# untitled.net
KiCad netlist of a schematic drawn in EAGLE
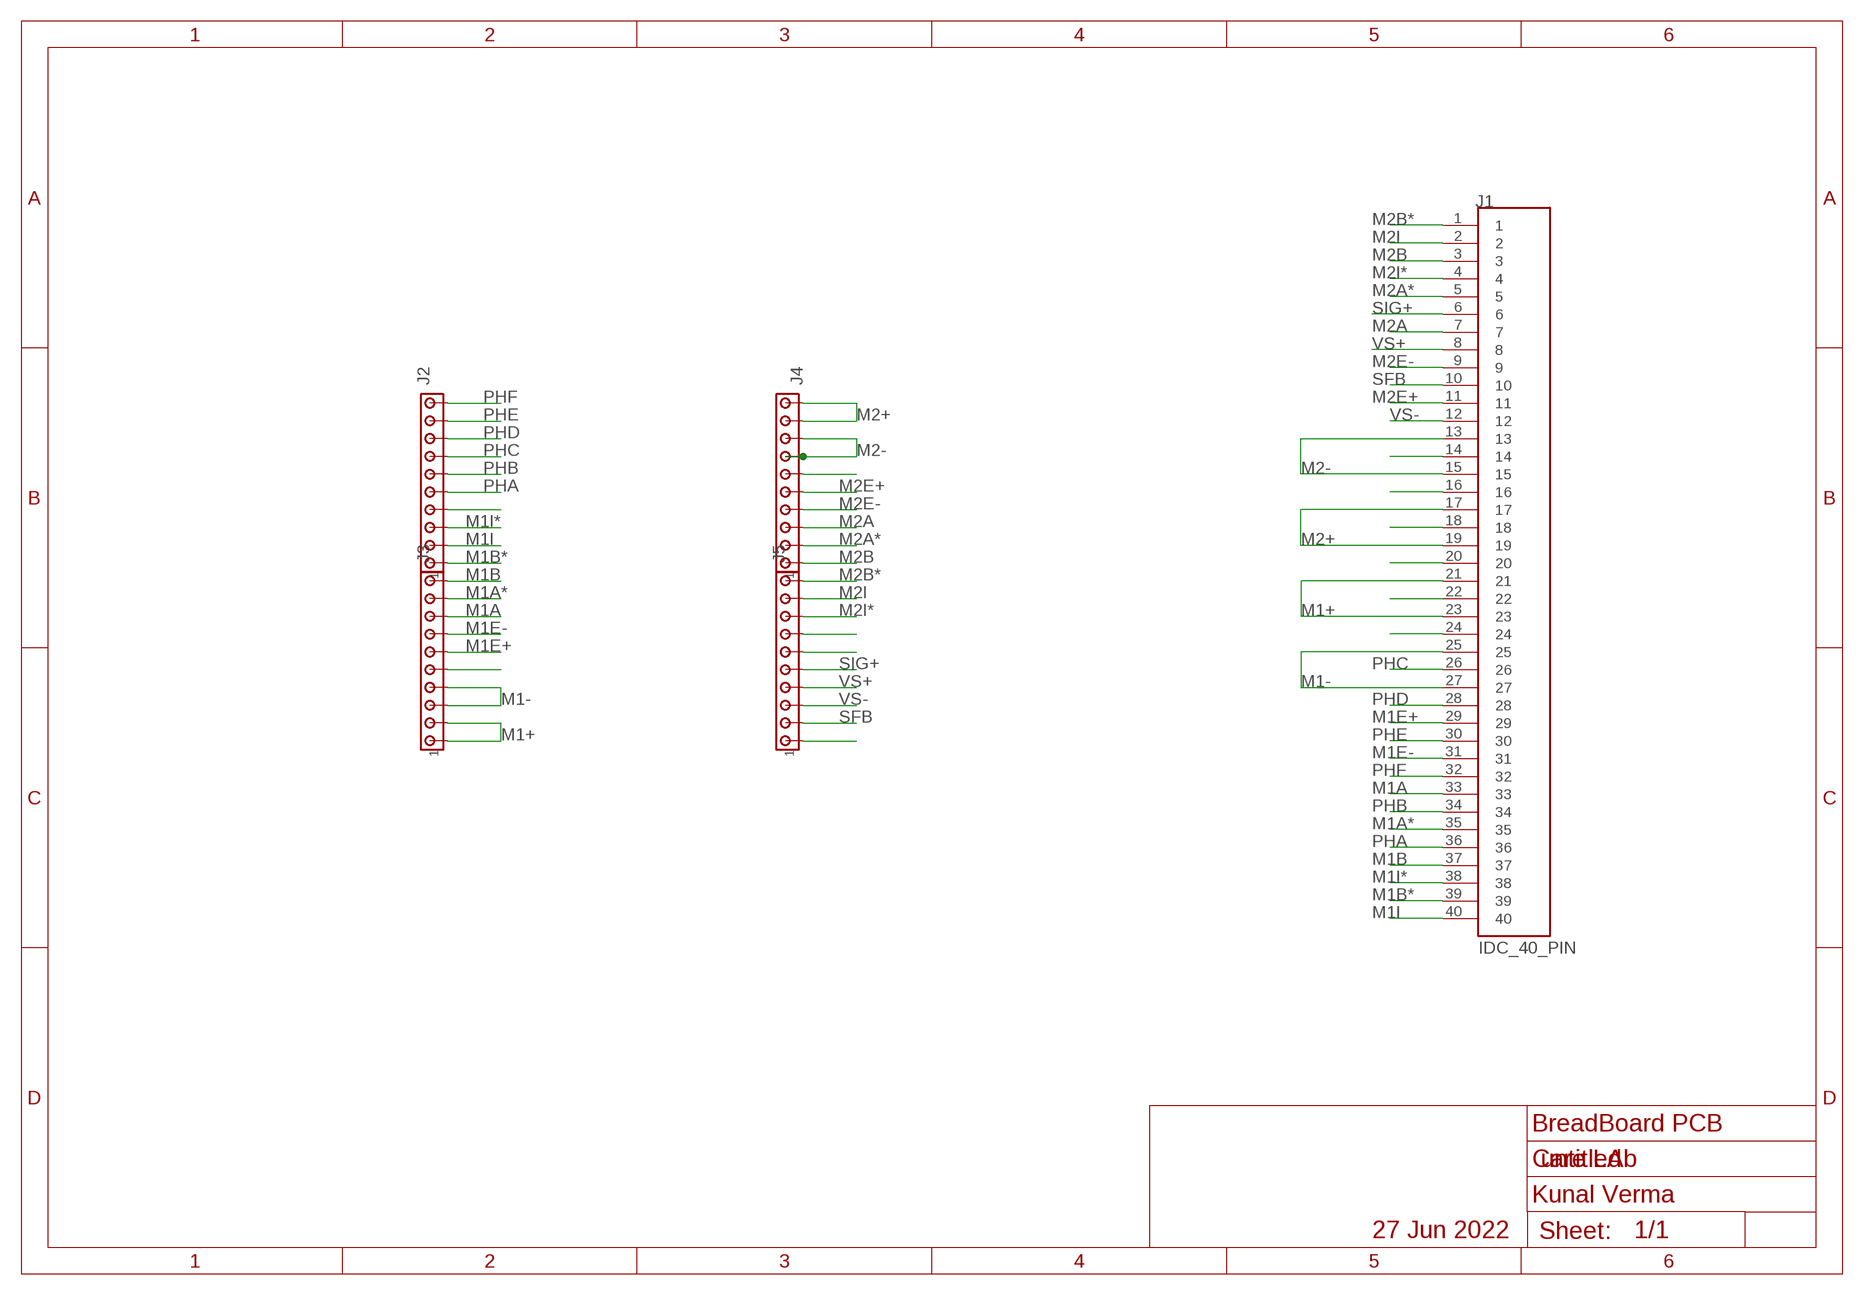
[diagram p0: schematic, sheet 1]

(export (version "E")
  (design (tool "Eeschema 10.0.6"))
  (components
    (comp (ref "J1")
      (value "IDC_40_PIN")
      (footprint "eagle-import:TE_3-1761605-3")
      (fields (field (name "COMMENT") "3-1761605-3") (field (name "MF") "TE Connectivity"))
      (libsource (lib "eagle-import") (part "IDC_40_PIN"))
    )
    (comp (ref "J2")
      (value "MTA10-100")
      (footprint "eagle-import:10X10MTA")
      (libsource (lib "eagle-import") (part "MTA10-100"))
    )
    (comp (ref "J3")
      (value "MTA10-100")
      (footprint "eagle-import:10X10MTA")
      (libsource (lib "eagle-import") (part "MTA10-100"))
    )
    (comp (ref "J4")
      (value "MTA10-100")
      (footprint "eagle-import:10X10MTA")
      (libsource (lib "eagle-import") (part "MTA10-100"))
    )
    (comp (ref "J5")
      (value "MTA10-100")
      (footprint "eagle-import:10X10MTA")
      (libsource (lib "eagle-import") (part "MTA10-100"))
    )
  )
  (nets
    (net (code "1") (name "/M1+") (class "Default")
      (node (ref "J1") (pin "21") (pinfunction "21_21") (pintype "passive"))
      (node (ref "J1") (pin "23") (pinfunction "23_23") (pintype "passive"))
      (node (ref "J3") (pin "1") (pinfunction "1_1") (pintype "passive"))
      (node (ref "J3") (pin "2") (pinfunction "2_2") (pintype "passive"))
    )
    (net (code "2") (name "/M1-") (class "Default")
      (node (ref "J1") (pin "25") (pinfunction "25_25") (pintype "passive"))
      (node (ref "J1") (pin "27") (pinfunction "27_27") (pintype "passive"))
      (node (ref "J3") (pin "3") (pinfunction "3_3") (pintype "passive"))
      (node (ref "J3") (pin "4") (pinfunction "4_4") (pintype "passive"))
    )
    (net (code "3") (name "/M1A") (class "Default")
      (node (ref "J1") (pin "33") (pinfunction "33_33") (pintype "passive"))
      (node (ref "J3") (pin "8") (pinfunction "8_8") (pintype "passive"))
    )
    (net (code "4") (name "/M1A*") (class "Default")
      (node (ref "J1") (pin "35") (pinfunction "35_35") (pintype "passive"))
      (node (ref "J3") (pin "9") (pinfunction "9_9") (pintype "passive"))
    )
    (net (code "5") (name "/M1B") (class "Default")
      (node (ref "J1") (pin "37") (pinfunction "37_37") (pintype "passive"))
      (node (ref "J3") (pin "10") (pinfunction "10_10") (pintype "passive"))
    )
    (net (code "6") (name "/M1B*") (class "Default")
      (node (ref "J1") (pin "39") (pinfunction "39_39") (pintype "passive"))
      (node (ref "J2") (pin "1") (pinfunction "1_1") (pintype "passive"))
    )
    (net (code "7") (name "/M1E+") (class "Default")
      (node (ref "J1") (pin "29") (pinfunction "29_29") (pintype "passive"))
      (node (ref "J3") (pin "6") (pinfunction "6_6") (pintype "passive"))
    )
    (net (code "8") (name "/M1E-") (class "Default")
      (node (ref "J1") (pin "31") (pinfunction "31_31") (pintype "passive"))
      (node (ref "J3") (pin "7") (pinfunction "7_7") (pintype "passive"))
    )
    (net (code "9") (name "/M1I") (class "Default")
      (node (ref "J1") (pin "40") (pinfunction "40_40") (pintype "passive"))
      (node (ref "J2") (pin "2") (pinfunction "2_2") (pintype "passive"))
    )
    (net (code "10") (name "/M1I*") (class "Default")
      (node (ref "J1") (pin "38") (pinfunction "38_38") (pintype "passive"))
      (node (ref "J2") (pin "3") (pinfunction "3_3") (pintype "passive"))
    )
    (net (code "11") (name "/M2+") (class "Default")
      (node (ref "J1") (pin "17") (pinfunction "17_17") (pintype "passive"))
      (node (ref "J1") (pin "19") (pinfunction "19_19") (pintype "passive"))
      (node (ref "J4") (pin "10") (pinfunction "10_10") (pintype "passive"))
      (node (ref "J4") (pin "9") (pinfunction "9_9") (pintype "passive"))
    )
    (net (code "12") (name "/M2-") (class "Default")
      (node (ref "J1") (pin "13") (pinfunction "13_13") (pintype "passive"))
      (node (ref "J1") (pin "15") (pinfunction "15_15") (pintype "passive"))
      (node (ref "J4") (pin "7") (pinfunction "7_7") (pintype "passive"))
      (node (ref "J4") (pin "8") (pinfunction "8_8") (pintype "passive"))
    )
    (net (code "13") (name "/M2A") (class "Default")
      (node (ref "J1") (pin "7") (pinfunction "7_7") (pintype "passive"))
      (node (ref "J4") (pin "3") (pinfunction "3_3") (pintype "passive"))
    )
    (net (code "14") (name "/M2A*") (class "Default")
      (node (ref "J1") (pin "5") (pinfunction "5_5") (pintype "passive"))
      (node (ref "J4") (pin "2") (pinfunction "2_2") (pintype "passive"))
    )
    (net (code "15") (name "/M2B") (class "Default")
      (node (ref "J1") (pin "3") (pinfunction "3_3") (pintype "passive"))
      (node (ref "J4") (pin "1") (pinfunction "1_1") (pintype "passive"))
    )
    (net (code "16") (name "/M2B*") (class "Default")
      (node (ref "J1") (pin "1") (pinfunction "1_1") (pintype "passive"))
      (node (ref "J5") (pin "10") (pinfunction "10_10") (pintype "passive"))
    )
    (net (code "17") (name "/M2E+") (class "Default")
      (node (ref "J1") (pin "11") (pinfunction "11_11") (pintype "passive"))
      (node (ref "J4") (pin "5") (pinfunction "5_5") (pintype "passive"))
    )
    (net (code "18") (name "/M2E-") (class "Default")
      (node (ref "J1") (pin "9") (pinfunction "9_9") (pintype "passive"))
      (node (ref "J4") (pin "4") (pinfunction "4_4") (pintype "passive"))
    )
    (net (code "19") (name "/M2I") (class "Default")
      (node (ref "J1") (pin "2") (pinfunction "2_2") (pintype "passive"))
      (node (ref "J5") (pin "9") (pinfunction "9_9") (pintype "passive"))
    )
    (net (code "20") (name "/M2I*") (class "Default")
      (node (ref "J1") (pin "4") (pinfunction "4_4") (pintype "passive"))
      (node (ref "J5") (pin "8") (pinfunction "8_8") (pintype "passive"))
    )
    (net (code "21") (name "/PHA") (class "Default")
      (node (ref "J1") (pin "36") (pinfunction "36_36") (pintype "passive"))
      (node (ref "J2") (pin "5") (pinfunction "5_5") (pintype "passive"))
    )
    (net (code "22") (name "/PHB") (class "Default")
      (node (ref "J1") (pin "34") (pinfunction "34_34") (pintype "passive"))
      (node (ref "J2") (pin "6") (pinfunction "6_6") (pintype "passive"))
    )
    (net (code "23") (name "/PHC") (class "Default")
      (node (ref "J1") (pin "26") (pinfunction "26_26") (pintype "passive"))
      (node (ref "J2") (pin "7") (pinfunction "7_7") (pintype "passive"))
    )
    (net (code "24") (name "/PHD") (class "Default")
      (node (ref "J1") (pin "28") (pinfunction "28_28") (pintype "passive"))
      (node (ref "J2") (pin "8") (pinfunction "8_8") (pintype "passive"))
    )
    (net (code "25") (name "/PHE") (class "Default")
      (node (ref "J1") (pin "30") (pinfunction "30_30") (pintype "passive"))
      (node (ref "J2") (pin "9") (pinfunction "9_9") (pintype "passive"))
    )
    (net (code "26") (name "/PHF") (class "Default")
      (node (ref "J1") (pin "32") (pinfunction "32_32") (pintype "passive"))
      (node (ref "J2") (pin "10") (pinfunction "10_10") (pintype "passive"))
    )
    (net (code "27") (name "/SFB") (class "Default")
      (node (ref "J1") (pin "10") (pinfunction "10_10") (pintype "passive"))
      (node (ref "J5") (pin "2") (pinfunction "2_2") (pintype "passive"))
    )
    (net (code "28") (name "/SIG+") (class "Default")
      (node (ref "J1") (pin "6") (pinfunction "6_6") (pintype "passive"))
      (node (ref "J5") (pin "5") (pinfunction "5_5") (pintype "passive"))
    )
    (net (code "29") (name "/VS+") (class "Default")
      (node (ref "J1") (pin "8") (pinfunction "8_8") (pintype "passive"))
      (node (ref "J5") (pin "4") (pinfunction "4_4") (pintype "passive"))
    )
    (net (code "30") (name "/VS-") (class "Default")
      (node (ref "J1") (pin "12") (pinfunction "12_12") (pintype "passive"))
      (node (ref "J5") (pin "3") (pinfunction "3_3") (pintype "passive"))
    )
    (net (code "31") (name "unconnected-(J1-Pad14)") (class "Default")
      (node (ref "J1") (pin "14") (pinfunction "14_14") (pintype "passive"))
    )
    (net (code "32") (name "unconnected-(J1-Pad16)") (class "Default")
      (node (ref "J1") (pin "16") (pinfunction "16_16") (pintype "passive"))
    )
    (net (code "33") (name "unconnected-(J1-Pad18)") (class "Default")
      (node (ref "J1") (pin "18") (pinfunction "18_18") (pintype "passive"))
    )
    (net (code "34") (name "unconnected-(J1-Pad20)") (class "Default")
      (node (ref "J1") (pin "20") (pinfunction "20_20") (pintype "passive"))
    )
    (net (code "35") (name "unconnected-(J1-Pad22)") (class "Default")
      (node (ref "J1") (pin "22") (pinfunction "22_22") (pintype "passive"))
    )
    (net (code "36") (name "unconnected-(J1-Pad24)") (class "Default")
      (node (ref "J1") (pin "24") (pinfunction "24_24") (pintype "passive"))
    )
    (net (code "37") (name "unconnected-(J2-Pad4)") (class "Default")
      (node (ref "J2") (pin "4") (pinfunction "4_4") (pintype "passive"))
    )
    (net (code "38") (name "unconnected-(J3-Pad5)") (class "Default")
      (node (ref "J3") (pin "5") (pinfunction "5_5") (pintype "passive"))
    )
    (net (code "39") (name "unconnected-(J4-Pad6)") (class "Default")
      (node (ref "J4") (pin "6") (pinfunction "6_6") (pintype "passive"))
    )
    (net (code "40") (name "unconnected-(J5-Pad1)") (class "Default")
      (node (ref "J5") (pin "1") (pinfunction "1_1") (pintype "passive"))
    )
    (net (code "41") (name "unconnected-(J5-Pad6)") (class "Default")
      (node (ref "J5") (pin "6") (pinfunction "6_6") (pintype "passive"))
    )
    (net (code "42") (name "unconnected-(J5-Pad7)") (class "Default")
      (node (ref "J5") (pin "7") (pinfunction "7_7") (pintype "passive"))
    )
  )
)
